# binarywatch.net
KiCad netlist of a schematic drawn in EAGLE
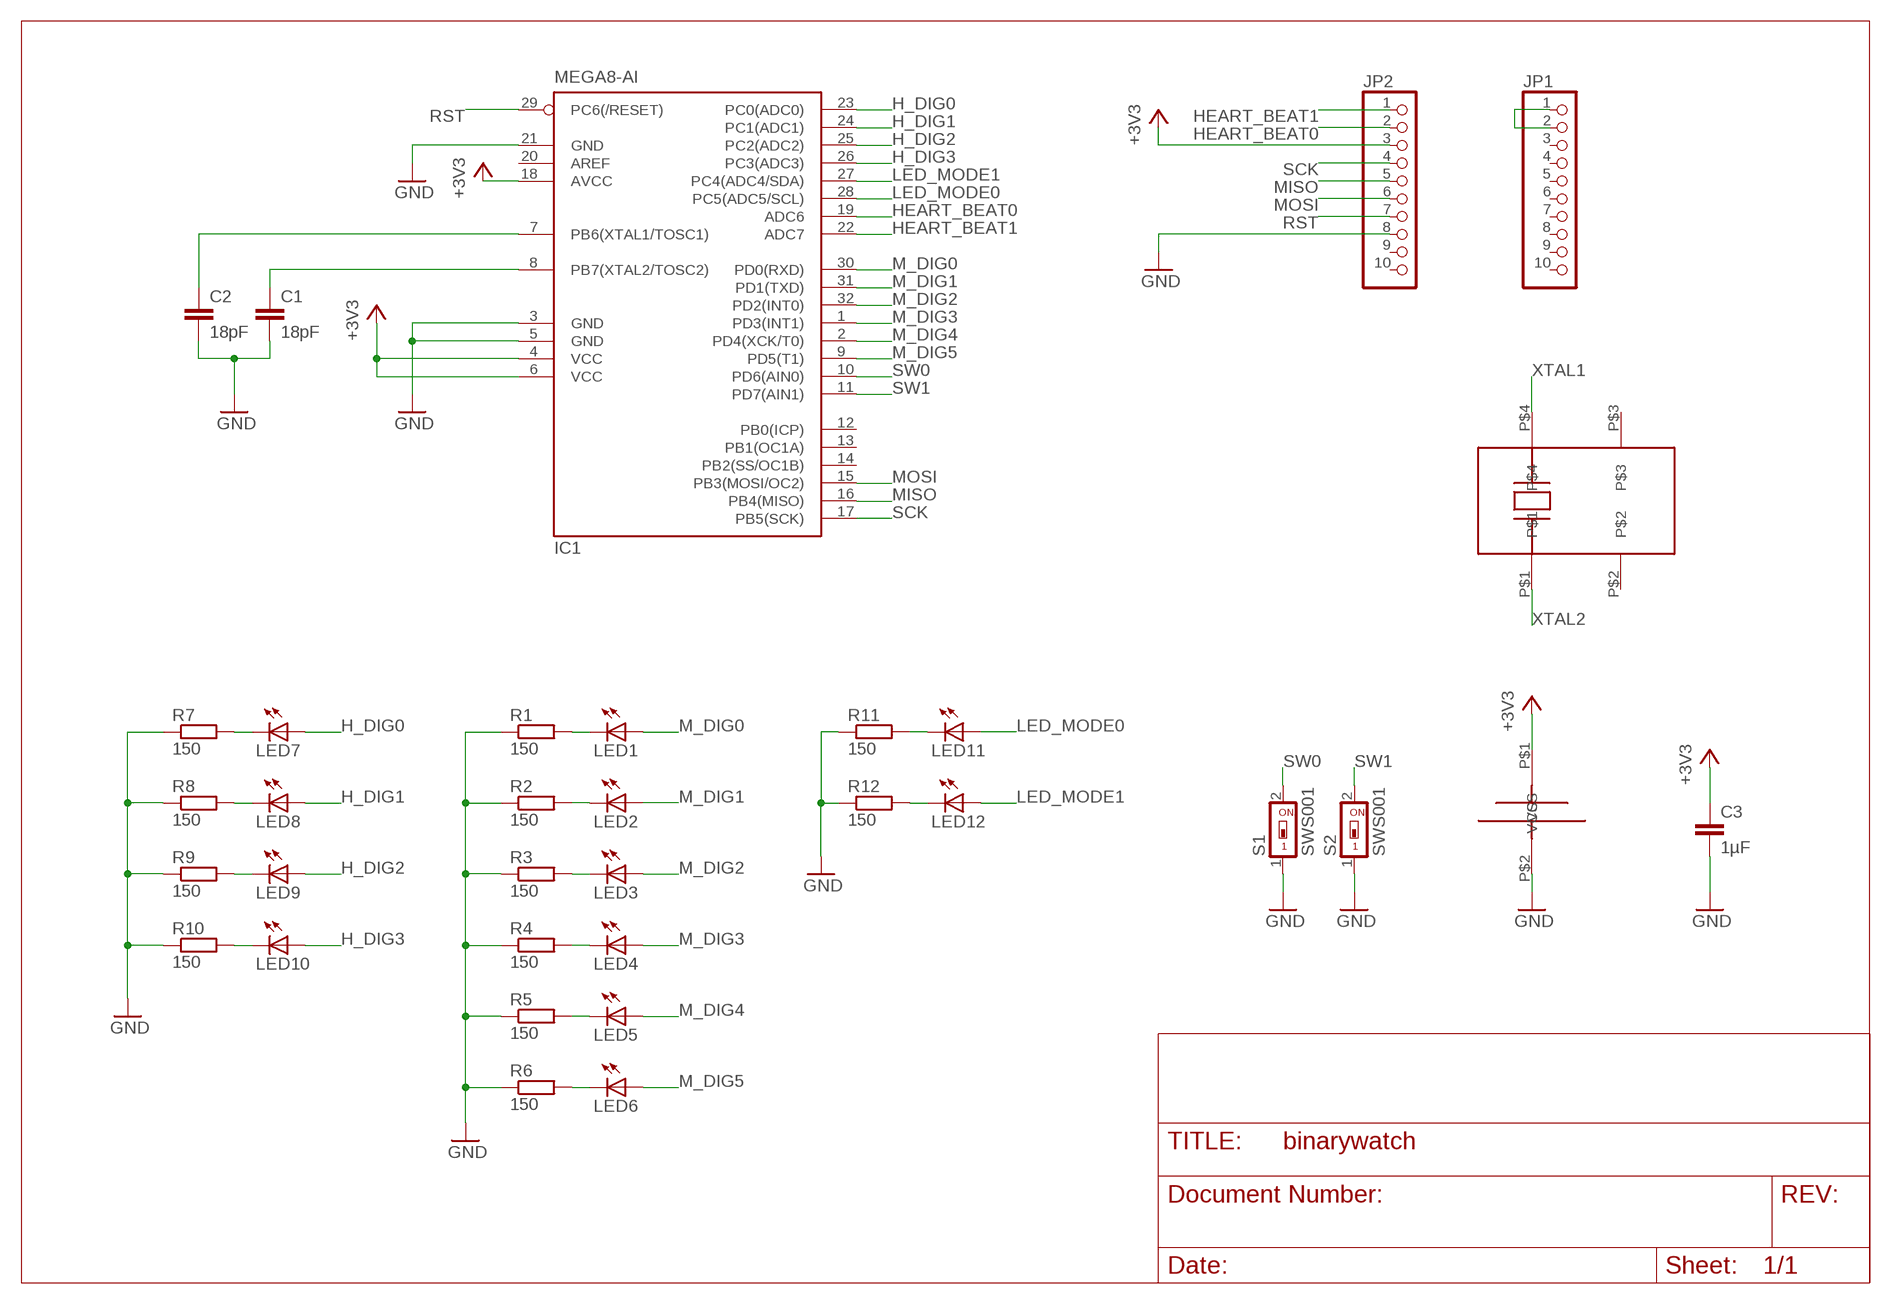
[diagram p0: schematic, sheet 1]

(export (version "E")
  (design (tool "Eeschema 10.0.6"))
  (components
    (comp (ref "C1")
      (value "18pF")
      (footprint "eagle-import:C0805")
      (libsource (lib "eagle-import") (part "C-EUC0805"))
    )
    (comp (ref "C2")
      (value "18pF")
      (footprint "eagle-import:C0805")
      (libsource (lib "eagle-import") (part "C-EUC0805"))
    )
    (comp (ref "C3")
      (value "1µF")
      (footprint "eagle-import:C0805")
      (libsource (lib "eagle-import") (part "C-EUC0805"))
    )
    (comp (ref "IC1")
      (value "MEGA8-AI")
      (footprint "eagle-import:TQFP32-08")
      (fields (field (name "MPN") "ATMEGA8-16AU"))
      (libsource (lib "eagle-import") (part "MEGA8-AI"))
    )
    (comp (ref "JP1")
      (value "PINHD-1X10")
      (footprint "eagle-import:1X10")
      (libsource (lib "eagle-import") (part "PINHD-1X10"))
    )
    (comp (ref "JP2")
      (value "PINHD-1X10")
      (footprint "eagle-import:1X10")
      (libsource (lib "eagle-import") (part "PINHD-1X10"))
    )
    (comp (ref "K1")
      (value "LZH20-1")
      (footprint "eagle-import:LZH20-1")
      (libsource (lib "eagle-import") (part "LZH20-1"))
    )
    (comp (ref "LED1")
      (value "LEDCHIPLED_0805")
      (footprint "eagle-import:CHIPLED_0805")
      (libsource (lib "eagle-import") (part "LEDCHIPLED_0805"))
    )
    (comp (ref "LED2")
      (value "LEDCHIPLED_0805")
      (footprint "eagle-import:CHIPLED_0805")
      (libsource (lib "eagle-import") (part "LEDCHIPLED_0805"))
    )
    (comp (ref "LED3")
      (value "LEDCHIPLED_0805")
      (footprint "eagle-import:CHIPLED_0805")
      (libsource (lib "eagle-import") (part "LEDCHIPLED_0805"))
    )
    (comp (ref "LED4")
      (value "LEDCHIPLED_0805")
      (footprint "eagle-import:CHIPLED_0805")
      (libsource (lib "eagle-import") (part "LEDCHIPLED_0805"))
    )
    (comp (ref "LED5")
      (value "LEDCHIPLED_0805")
      (footprint "eagle-import:CHIPLED_0805")
      (libsource (lib "eagle-import") (part "LEDCHIPLED_0805"))
    )
    (comp (ref "LED6")
      (value "LEDCHIPLED_0805")
      (footprint "eagle-import:CHIPLED_0805")
      (libsource (lib "eagle-import") (part "LEDCHIPLED_0805"))
    )
    (comp (ref "LED7")
      (value "LEDCHIPLED_0805")
      (footprint "eagle-import:CHIPLED_0805")
      (libsource (lib "eagle-import") (part "LEDCHIPLED_0805"))
    )
    (comp (ref "LED8")
      (value "LEDCHIPLED_0805")
      (footprint "eagle-import:CHIPLED_0805")
      (libsource (lib "eagle-import") (part "LEDCHIPLED_0805"))
    )
    (comp (ref "LED9")
      (value "LEDCHIPLED_0805")
      (footprint "eagle-import:CHIPLED_0805")
      (libsource (lib "eagle-import") (part "LEDCHIPLED_0805"))
    )
    (comp (ref "LED10")
      (value "LEDCHIPLED_0805")
      (footprint "eagle-import:CHIPLED_0805")
      (libsource (lib "eagle-import") (part "LEDCHIPLED_0805"))
    )
    (comp (ref "LED11")
      (value "LEDCHIPLED_0805")
      (footprint "eagle-import:CHIPLED_0805")
      (libsource (lib "eagle-import") (part "LEDCHIPLED_0805"))
    )
    (comp (ref "LED12")
      (value "LEDCHIPLED_0805")
      (footprint "eagle-import:CHIPLED_0805")
      (libsource (lib "eagle-import") (part "LEDCHIPLED_0805"))
    )
    (comp (ref "R1")
      (value "150")
      (footprint "eagle-import:R0805")
      (libsource (lib "eagle-import") (part "R-EU_R0805"))
    )
    (comp (ref "R2")
      (value "150")
      (footprint "eagle-import:R0805")
      (libsource (lib "eagle-import") (part "R-EU_R0805"))
    )
    (comp (ref "R3")
      (value "150")
      (footprint "eagle-import:R0805")
      (libsource (lib "eagle-import") (part "R-EU_R0805"))
    )
    (comp (ref "R4")
      (value "150")
      (footprint "eagle-import:R0805")
      (libsource (lib "eagle-import") (part "R-EU_R0805"))
    )
    (comp (ref "R5")
      (value "150")
      (footprint "eagle-import:R0805")
      (libsource (lib "eagle-import") (part "R-EU_R0805"))
    )
    (comp (ref "R6")
      (value "150")
      (footprint "eagle-import:R0805")
      (libsource (lib "eagle-import") (part "R-EU_R0805"))
    )
    (comp (ref "R7")
      (value "150")
      (footprint "eagle-import:R0805")
      (libsource (lib "eagle-import") (part "R-EU_R0805"))
    )
    (comp (ref "R8")
      (value "150")
      (footprint "eagle-import:R0805")
      (libsource (lib "eagle-import") (part "R-EU_R0805"))
    )
    (comp (ref "R9")
      (value "150")
      (footprint "eagle-import:R0805")
      (libsource (lib "eagle-import") (part "R-EU_R0805"))
    )
    (comp (ref "R10")
      (value "150")
      (footprint "eagle-import:R0805")
      (libsource (lib "eagle-import") (part "R-EU_R0805"))
    )
    (comp (ref "R11")
      (value "150")
      (footprint "eagle-import:R0805")
      (libsource (lib "eagle-import") (part "R-EU_R0805"))
    )
    (comp (ref "R12")
      (value "150")
      (footprint "eagle-import:R0805")
      (libsource (lib "eagle-import") (part "R-EU_R0805"))
    )
    (comp (ref "S1")
      (value "SWS001")
      (footprint "eagle-import:SMS-001")
      (libsource (lib "eagle-import") (part "SWS001"))
    )
    (comp (ref "S2")
      (value "SWS001")
      (footprint "eagle-import:SMS-001")
      (libsource (lib "eagle-import") (part "SWS001"))
    )
    (comp (ref "U$1")
      (value "32768KHZ")
      (footprint "eagle-import:32768KHZ")
      (libsource (lib "eagle-import") (part "32768KHZ"))
    )
  )
  (nets
    (net (code "1") (name "+3V3") (class "Default")
      (node (ref "C3") (pin "1") (pinfunction "1_1") (pintype "passive"))
      (node (ref "IC1") (pin "18") (pinfunction "AVCC_18") (pintype "power_in"))
      (node (ref "IC1") (pin "4") (pinfunction "VCC_4") (pintype "power_in"))
      (node (ref "IC1") (pin "6") (pinfunction "VCC_6") (pintype "power_in"))
      (node (ref "JP2") (pin "3") (pinfunction "3_3") (pintype "passive"))
      (node (ref "K1") (pin "P$1") (pinfunction "VCC_P$1") (pintype "power_in"))
    )
    (net (code "2") (name "/HEART_BEAT0") (class "Default")
      (node (ref "IC1") (pin "19") (pinfunction "ADC6_19") (pintype "bidirectional"))
      (node (ref "JP2") (pin "2") (pinfunction "2_2") (pintype "passive"))
    )
    (net (code "3") (name "/HEART_BEAT1") (class "Default")
      (node (ref "IC1") (pin "22") (pinfunction "ADC7_22") (pintype "bidirectional"))
      (node (ref "JP2") (pin "1") (pinfunction "1_1") (pintype "passive"))
    )
    (net (code "4") (name "/H_DIG0") (class "Default")
      (node (ref "IC1") (pin "23") (pinfunction "PC0(ADC0)_23") (pintype "bidirectional"))
      (node (ref "LED7") (pin "A") (pinfunction "A_A") (pintype "passive"))
    )
    (net (code "5") (name "/H_DIG1") (class "Default")
      (node (ref "IC1") (pin "24") (pinfunction "PC1(ADC1)_24") (pintype "bidirectional"))
      (node (ref "LED8") (pin "A") (pinfunction "A_A") (pintype "passive"))
    )
    (net (code "6") (name "/H_DIG2") (class "Default")
      (node (ref "IC1") (pin "25") (pinfunction "PC2(ADC2)_25") (pintype "bidirectional"))
      (node (ref "LED9") (pin "A") (pinfunction "A_A") (pintype "passive"))
    )
    (net (code "7") (name "/H_DIG3") (class "Default")
      (node (ref "IC1") (pin "26") (pinfunction "PC3(ADC3)_26") (pintype "bidirectional"))
      (node (ref "LED10") (pin "A") (pinfunction "A_A") (pintype "passive"))
    )
    (net (code "8") (name "/LED_MODE0") (class "Default")
      (node (ref "IC1") (pin "28") (pinfunction "PC5(ADC5/SCL)_28") (pintype "bidirectional"))
      (node (ref "LED11") (pin "A") (pinfunction "A_A") (pintype "passive"))
    )
    (net (code "9") (name "/LED_MODE1") (class "Default")
      (node (ref "IC1") (pin "27") (pinfunction "PC4(ADC4/SDA)_27") (pintype "bidirectional"))
      (node (ref "LED12") (pin "A") (pinfunction "A_A") (pintype "passive"))
    )
    (net (code "10") (name "/MISO") (class "Default")
      (node (ref "IC1") (pin "16") (pinfunction "PB4(MISO)_16") (pintype "bidirectional"))
      (node (ref "JP2") (pin "5") (pinfunction "5_5") (pintype "passive"))
    )
    (net (code "11") (name "/MOSI") (class "Default")
      (node (ref "IC1") (pin "15") (pinfunction "PB3(MOSI/OC2)_15") (pintype "bidirectional"))
      (node (ref "JP2") (pin "6") (pinfunction "6_6") (pintype "passive"))
    )
    (net (code "12") (name "/M_DIG0") (class "Default")
      (node (ref "IC1") (pin "30") (pinfunction "PD0(RXD)_30") (pintype "bidirectional"))
      (node (ref "LED1") (pin "A") (pinfunction "A_A") (pintype "passive"))
    )
    (net (code "13") (name "/M_DIG1") (class "Default")
      (node (ref "IC1") (pin "31") (pinfunction "PD1(TXD)_31") (pintype "bidirectional"))
      (node (ref "LED2") (pin "A") (pinfunction "A_A") (pintype "passive"))
    )
    (net (code "14") (name "/M_DIG2") (class "Default")
      (node (ref "IC1") (pin "32") (pinfunction "PD2(INT0)_32") (pintype "bidirectional"))
      (node (ref "LED3") (pin "A") (pinfunction "A_A") (pintype "passive"))
    )
    (net (code "15") (name "/M_DIG3") (class "Default")
      (node (ref "IC1") (pin "1") (pinfunction "PD3(INT1)_1") (pintype "bidirectional"))
      (node (ref "LED4") (pin "A") (pinfunction "A_A") (pintype "passive"))
    )
    (net (code "16") (name "/M_DIG4") (class "Default")
      (node (ref "IC1") (pin "2") (pinfunction "PD4(XCK/T0)_2") (pintype "bidirectional"))
      (node (ref "LED5") (pin "A") (pinfunction "A_A") (pintype "passive"))
    )
    (net (code "17") (name "/M_DIG5") (class "Default")
      (node (ref "IC1") (pin "9") (pinfunction "PD5(T1)_9") (pintype "bidirectional"))
      (node (ref "LED6") (pin "A") (pinfunction "A_A") (pintype "passive"))
    )
    (net (code "18") (name "/RST") (class "Default")
      (node (ref "IC1") (pin "29") (pinfunction "PC6(/RESET)_29") (pintype "bidirectional"))
      (node (ref "JP2") (pin "7") (pinfunction "7_7") (pintype "passive"))
    )
    (net (code "19") (name "/SCK") (class "Default")
      (node (ref "IC1") (pin "17") (pinfunction "PB5(SCK)_17") (pintype "bidirectional"))
      (node (ref "JP2") (pin "4") (pinfunction "4_4") (pintype "passive"))
    )
    (net (code "20") (name "/SW0") (class "Default")
      (node (ref "IC1") (pin "10") (pinfunction "PD6(AIN0)_10") (pintype "bidirectional"))
      (node (ref "S1") (pin "2") (pinfunction "2_2") (pintype "passive"))
    )
    (net (code "21") (name "/SW1") (class "Default")
      (node (ref "IC1") (pin "11") (pinfunction "PD7(AIN1)_11") (pintype "bidirectional"))
      (node (ref "S2") (pin "2") (pinfunction "2_2") (pintype "passive"))
    )
    (net (code "22") (name "/XTAL1") (class "Default")
      (node (ref "C2") (pin "1") (pinfunction "1_1") (pintype "passive"))
      (node (ref "IC1") (pin "7") (pinfunction "PB6(XTAL1/TOSC1)_7") (pintype "bidirectional"))
      (node (ref "U$1") (pin "P$4") (pinfunction "P$4_P$4") (pintype "output"))
    )
    (net (code "23") (name "/XTAL2") (class "Default")
      (node (ref "C1") (pin "1") (pinfunction "1_1") (pintype "passive"))
      (node (ref "IC1") (pin "8") (pinfunction "PB7(XTAL2/TOSC2)_8") (pintype "bidirectional"))
      (node (ref "U$1") (pin "P$1") (pinfunction "P$1_P$1") (pintype "output"))
    )
    (net (code "24") (name "GND") (class "Default")
      (node (ref "C1") (pin "2") (pinfunction "2_2") (pintype "passive"))
      (node (ref "C2") (pin "2") (pinfunction "2_2") (pintype "passive"))
      (node (ref "C3") (pin "2") (pinfunction "2_2") (pintype "passive"))
      (node (ref "IC1") (pin "21") (pinfunction "GND_21") (pintype "power_in"))
      (node (ref "IC1") (pin "3") (pinfunction "GND_3") (pintype "power_in"))
      (node (ref "IC1") (pin "5") (pinfunction "GND_5") (pintype "power_in"))
      (node (ref "JP2") (pin "8") (pinfunction "8_8") (pintype "passive"))
      (node (ref "K1") (pin "P$2") (pinfunction "VSS_P$2") (pintype "power_in"))
      (node (ref "R1") (pin "1") (pinfunction "1_1") (pintype "passive"))
      (node (ref "R10") (pin "1") (pinfunction "1_1") (pintype "passive"))
      (node (ref "R11") (pin "1") (pinfunction "1_1") (pintype "passive"))
      (node (ref "R12") (pin "1") (pinfunction "1_1") (pintype "passive"))
      (node (ref "R2") (pin "1") (pinfunction "1_1") (pintype "passive"))
      (node (ref "R3") (pin "1") (pinfunction "1_1") (pintype "passive"))
      (node (ref "R4") (pin "1") (pinfunction "1_1") (pintype "passive"))
      (node (ref "R5") (pin "1") (pinfunction "1_1") (pintype "passive"))
      (node (ref "R6") (pin "1") (pinfunction "1_1") (pintype "passive"))
      (node (ref "R7") (pin "1") (pinfunction "1_1") (pintype "passive"))
      (node (ref "R8") (pin "1") (pinfunction "1_1") (pintype "passive"))
      (node (ref "R9") (pin "1") (pinfunction "1_1") (pintype "passive"))
      (node (ref "S1") (pin "1") (pinfunction "1_1") (pintype "passive"))
      (node (ref "S2") (pin "1") (pinfunction "1_1") (pintype "passive"))
    )
    (net (code "25") (name "Net-(JP1-Pad1)") (class "Default")
      (node (ref "JP1") (pin "1") (pinfunction "1_1") (pintype "passive"))
      (node (ref "JP1") (pin "2") (pinfunction "2_2") (pintype "passive"))
    )
    (net (code "26") (name "Net-(LED1-PadC)") (class "Default")
      (node (ref "LED1") (pin "C") (pinfunction "C_C") (pintype "passive"))
      (node (ref "R1") (pin "2") (pinfunction "2_2") (pintype "passive"))
    )
    (net (code "27") (name "Net-(LED2-PadC)") (class "Default")
      (node (ref "LED2") (pin "C") (pinfunction "C_C") (pintype "passive"))
      (node (ref "R2") (pin "2") (pinfunction "2_2") (pintype "passive"))
    )
    (net (code "28") (name "Net-(LED3-PadC)") (class "Default")
      (node (ref "LED3") (pin "C") (pinfunction "C_C") (pintype "passive"))
      (node (ref "R3") (pin "2") (pinfunction "2_2") (pintype "passive"))
    )
    (net (code "29") (name "Net-(LED4-PadC)") (class "Default")
      (node (ref "LED4") (pin "C") (pinfunction "C_C") (pintype "passive"))
      (node (ref "R4") (pin "2") (pinfunction "2_2") (pintype "passive"))
    )
    (net (code "30") (name "Net-(LED5-PadC)") (class "Default")
      (node (ref "LED5") (pin "C") (pinfunction "C_C") (pintype "passive"))
      (node (ref "R5") (pin "2") (pinfunction "2_2") (pintype "passive"))
    )
    (net (code "31") (name "Net-(LED6-PadC)") (class "Default")
      (node (ref "LED6") (pin "C") (pinfunction "C_C") (pintype "passive"))
      (node (ref "R6") (pin "2") (pinfunction "2_2") (pintype "passive"))
    )
    (net (code "32") (name "Net-(LED7-PadC)") (class "Default")
      (node (ref "LED7") (pin "C") (pinfunction "C_C") (pintype "passive"))
      (node (ref "R7") (pin "2") (pinfunction "2_2") (pintype "passive"))
    )
    (net (code "33") (name "Net-(LED8-PadC)") (class "Default")
      (node (ref "LED8") (pin "C") (pinfunction "C_C") (pintype "passive"))
      (node (ref "R8") (pin "2") (pinfunction "2_2") (pintype "passive"))
    )
    (net (code "34") (name "Net-(LED9-PadC)") (class "Default")
      (node (ref "LED9") (pin "C") (pinfunction "C_C") (pintype "passive"))
      (node (ref "R9") (pin "2") (pinfunction "2_2") (pintype "passive"))
    )
    (net (code "35") (name "Net-(LED10-PadC)") (class "Default")
      (node (ref "LED10") (pin "C") (pinfunction "C_C") (pintype "passive"))
      (node (ref "R10") (pin "2") (pinfunction "2_2") (pintype "passive"))
    )
    (net (code "36") (name "Net-(LED11-PadC)") (class "Default")
      (node (ref "LED11") (pin "C") (pinfunction "C_C") (pintype "passive"))
      (node (ref "R11") (pin "2") (pinfunction "2_2") (pintype "passive"))
    )
    (net (code "37") (name "Net-(LED12-PadC)") (class "Default")
      (node (ref "LED12") (pin "C") (pinfunction "C_C") (pintype "passive"))
      (node (ref "R12") (pin "2") (pinfunction "2_2") (pintype "passive"))
    )
    (net (code "38") (name "unconnected-(IC1-AREF-Pad20)") (class "Default")
      (node (ref "IC1") (pin "20") (pinfunction "AREF_20") (pintype "passive"))
    )
    (net (code "39") (name "unconnected-(IC1-PB0(ICP)-Pad12)") (class "Default")
      (node (ref "IC1") (pin "12") (pinfunction "PB0(ICP)_12") (pintype "bidirectional"))
    )
    (net (code "40") (name "unconnected-(IC1-PB1(OC1A)-Pad13)") (class "Default")
      (node (ref "IC1") (pin "13") (pinfunction "PB1(OC1A)_13") (pintype "bidirectional"))
    )
    (net (code "41") (name "unconnected-(IC1-PB2(SS{slash}OC1B)-Pad14)") (class "Default")
      (node (ref "IC1") (pin "14") (pinfunction "PB2(SS/OC1B)_14") (pintype "bidirectional"))
    )
    (net (code "42") (name "unconnected-(JP1-Pad3)") (class "Default")
      (node (ref "JP1") (pin "3") (pinfunction "3_3") (pintype "passive"))
    )
    (net (code "43") (name "unconnected-(JP1-Pad4)") (class "Default")
      (node (ref "JP1") (pin "4") (pinfunction "4_4") (pintype "passive"))
    )
    (net (code "44") (name "unconnected-(JP1-Pad5)") (class "Default")
      (node (ref "JP1") (pin "5") (pinfunction "5_5") (pintype "passive"))
    )
    (net (code "45") (name "unconnected-(JP1-Pad6)") (class "Default")
      (node (ref "JP1") (pin "6") (pinfunction "6_6") (pintype "passive"))
    )
    (net (code "46") (name "unconnected-(JP1-Pad7)") (class "Default")
      (node (ref "JP1") (pin "7") (pinfunction "7_7") (pintype "passive"))
    )
    (net (code "47") (name "unconnected-(JP1-Pad8)") (class "Default")
      (node (ref "JP1") (pin "8") (pinfunction "8_8") (pintype "passive"))
    )
    (net (code "48") (name "unconnected-(JP1-Pad9)") (class "Default")
      (node (ref "JP1") (pin "9") (pinfunction "9_9") (pintype "passive"))
    )
    (net (code "49") (name "unconnected-(JP1-Pad10)") (class "Default")
      (node (ref "JP1") (pin "10") (pinfunction "10_10") (pintype "passive"))
    )
    (net (code "50") (name "unconnected-(JP2-Pad9)") (class "Default")
      (node (ref "JP2") (pin "9") (pinfunction "9_9") (pintype "passive"))
    )
    (net (code "51") (name "unconnected-(JP2-Pad10)") (class "Default")
      (node (ref "JP2") (pin "10") (pinfunction "10_10") (pintype "passive"))
    )
    (net (code "52") (name "unconnected-(U$1-PadP$2)") (class "Default")
      (node (ref "U$1") (pin "P$2") (pinfunction "P$2_P$2") (pintype "output"))
    )
    (net (code "53") (name "unconnected-(U$1-PadP$3)") (class "Default")
      (node (ref "U$1") (pin "P$3") (pinfunction "P$3_P$3") (pintype "output"))
    )
  )
)
